# Schaltplan_VoltageLevelShifter_version3_.net
KiCad netlist of a schematic drawn in EAGLE
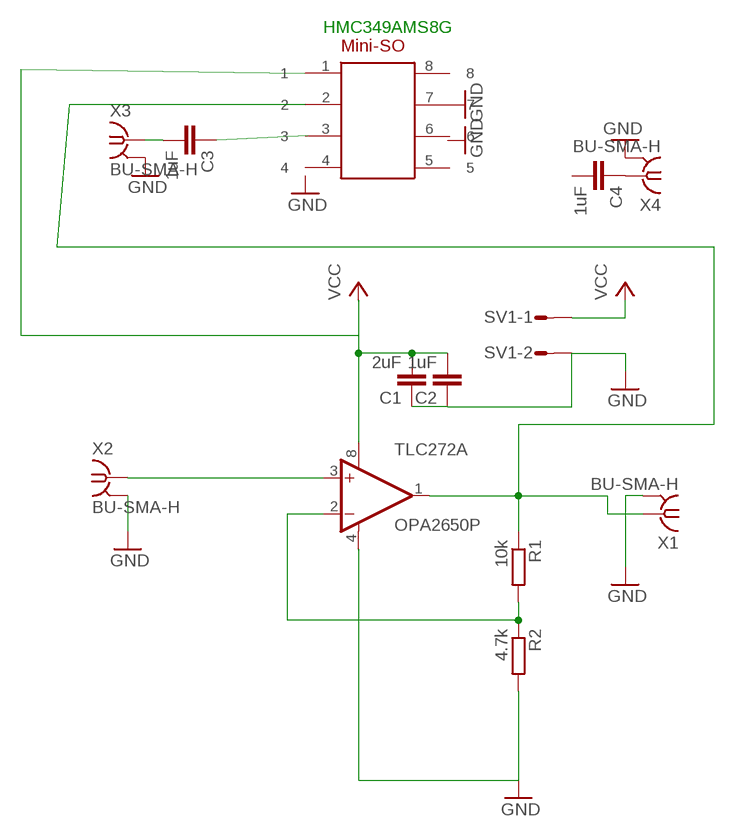
[diagram p0: schematic, sheet 1]

(export (version "E")
  (design (tool "Eeschema 10.0.6"))
  (components
    (comp (ref "C1")
      (value "2uF")
      (footprint "eagle-import:YC7B5")
      (libsource (lib "eagle-import") (part "CYYC7B5"))
    )
    (comp (ref "C2")
      (value "1uF")
      (footprint "eagle-import:YC7B5")
      (libsource (lib "eagle-import") (part "CYYC7B5"))
    )
    (comp (ref "C3")
      (value "1uF")
      (footprint "eagle-import:YC7B5")
      (libsource (lib "eagle-import") (part "CYYC7B5"))
    )
    (comp (ref "C4")
      (value "1uF")
      (footprint "eagle-import:YC7B5")
      (libsource (lib "eagle-import") (part "CYYC7B5"))
    )
    (comp (ref "HMC349AMS8G")
      (value "MINI-SO")
      (footprint "eagle-import:MINI-SO")
      (libsource (lib "eagle-import") (part "MINI-SO"))
    )
    (comp (ref "R1")
      (value "10k")
      (footprint "eagle-import:0207_12")
      (libsource (lib "eagle-import") (part "R-EU_0207/12"))
    )
    (comp (ref "R2")
      (value "4.7k")
      (footprint "eagle-import:0207_12")
      (libsource (lib "eagle-import") (part "R-EU_0207/12"))
    )
    (comp (ref "SV1")
      (value "S02P")
      (footprint "eagle-import:S02P")
      (libsource (lib "eagle-import") (part "S02P"))
    )
    (comp (ref "TLC272")
      (value "OPA2650P")
      (footprint "eagle-import:DIL08")
      (fields (field (name "MPN") "AD8056ANZ"))
      (libsource (lib "eagle-import") (part "OPA2650P"))
    )
    (comp (ref "X1")
      (value "BU-SMA-H")
      (footprint "eagle-import:BU-SMA-H")
      (libsource (lib "eagle-import") (part "BU-SMA-H"))
    )
    (comp (ref "X2")
      (value "BU-SMA-H")
      (footprint "eagle-import:BU-SMA-H")
      (libsource (lib "eagle-import") (part "BU-SMA-H"))
    )
    (comp (ref "X3")
      (value "BU-SMA-H")
      (footprint "eagle-import:BU-SMA-H")
      (libsource (lib "eagle-import") (part "BU-SMA-H"))
    )
    (comp (ref "X4")
      (value "BU-SMA-H")
      (footprint "eagle-import:BU-SMA-H")
      (libsource (lib "eagle-import") (part "BU-SMA-H"))
    )
  )
  (nets
    (net (code "1") (name "GND") (class "Default")
      (node (ref "C1") (pin "1") (pinfunction "1_1") (pintype "passive"))
      (node (ref "C2") (pin "1") (pinfunction "1_1") (pintype "passive"))
      (node (ref "R2") (pin "2") (pinfunction "2_2") (pintype "passive"))
      (node (ref "SV1") (pin "2") (pinfunction "S_2") (pintype "passive"))
      (node (ref "TLC272") (pin "4") (pinfunction "V-_4") (pintype "power_in"))
      (node (ref "X1") (pin "2") (pinfunction "2_2") (pintype "passive"))
      (node (ref "X1") (pin "3") (pinfunction "2_3") (pintype "passive"))
      (node (ref "X1") (pin "4") (pinfunction "2_4") (pintype "passive"))
      (node (ref "X1") (pin "5") (pinfunction "2_5") (pintype "passive"))
      (node (ref "X2") (pin "2") (pinfunction "2_2") (pintype "passive"))
      (node (ref "X2") (pin "3") (pinfunction "2_3") (pintype "passive"))
      (node (ref "X2") (pin "4") (pinfunction "2_4") (pintype "passive"))
      (node (ref "X2") (pin "5") (pinfunction "2_5") (pintype "passive"))
      (node (ref "X3") (pin "2") (pinfunction "2_2") (pintype "passive"))
      (node (ref "X3") (pin "3") (pinfunction "2_3") (pintype "passive"))
      (node (ref "X3") (pin "4") (pinfunction "2_4") (pintype "passive"))
      (node (ref "X3") (pin "5") (pinfunction "2_5") (pintype "passive"))
      (node (ref "X4") (pin "2") (pinfunction "2_2") (pintype "passive"))
      (node (ref "X4") (pin "3") (pinfunction "2_3") (pintype "passive"))
      (node (ref "X4") (pin "4") (pinfunction "2_4") (pintype "passive"))
      (node (ref "X4") (pin "5") (pinfunction "2_5") (pintype "passive"))
    )
    (net (code "2") (name "Net-(C3-Pad2)") (class "Default")
      (node (ref "C3") (pin "2") (pinfunction "2_2") (pintype "passive"))
      (node (ref "X3") (pin "1") (pinfunction "1_1") (pintype "passive"))
    )
    (net (code "3") (name "Net-(C4-Pad1)") (class "Default")
      (node (ref "C4") (pin "1") (pinfunction "1_1") (pintype "passive"))
      (node (ref "X4") (pin "1") (pinfunction "1_1") (pintype "passive"))
    )
    (net (code "4") (name "Net-(TLC272A-+IN)") (class "Default")
      (node (ref "TLC272") (pin "3") (pinfunction "+IN_3") (pintype "input"))
      (node (ref "X2") (pin "1") (pinfunction "1_1") (pintype "passive"))
    )
    (net (code "5") (name "Net-(TLC272A--IN)") (class "Default")
      (node (ref "R1") (pin "2") (pinfunction "2_2") (pintype "passive"))
      (node (ref "R2") (pin "1") (pinfunction "1_1") (pintype "passive"))
      (node (ref "TLC272") (pin "2") (pinfunction "-IN_2") (pintype "input"))
    )
    (net (code "6") (name "Net-(TLC272A-OUT)") (class "Default")
      (node (ref "R1") (pin "1") (pinfunction "1_1") (pintype "passive"))
      (node (ref "TLC272") (pin "1") (pinfunction "OUT_1") (pintype "output"))
      (node (ref "X1") (pin "1") (pinfunction "1_1") (pintype "passive"))
    )
    (net (code "7") (name "VCC") (class "Default")
      (node (ref "C1") (pin "2") (pinfunction "2_2") (pintype "passive"))
      (node (ref "C2") (pin "2") (pinfunction "2_2") (pintype "passive"))
      (node (ref "SV1") (pin "1") (pinfunction "S_1") (pintype "passive"))
      (node (ref "TLC272") (pin "8") (pinfunction "V+_8") (pintype "power_in"))
    )
    (net (code "8") (name "unconnected-(C3-Pad1)") (class "Default")
      (node (ref "C3") (pin "1") (pinfunction "1_1") (pintype "passive"))
    )
    (net (code "9") (name "unconnected-(C4-Pad2)") (class "Default")
      (node (ref "C4") (pin "2") (pinfunction "2_2") (pintype "passive"))
    )
    (net (code "10") (name "unconnected-(HMC349AMS8G-Pad1)") (class "Default")
      (node (ref "HMC349AMS8G") (pin "1") (pinfunction "1_1") (pintype "bidirectional"))
    )
    (net (code "11") (name "unconnected-(HMC349AMS8G-Pad2)") (class "Default")
      (node (ref "HMC349AMS8G") (pin "2") (pinfunction "2_2") (pintype "bidirectional"))
    )
    (net (code "12") (name "unconnected-(HMC349AMS8G-Pad3)") (class "Default")
      (node (ref "HMC349AMS8G") (pin "3") (pinfunction "3_3") (pintype "bidirectional"))
    )
    (net (code "13") (name "unconnected-(HMC349AMS8G-Pad4)") (class "Default")
      (node (ref "HMC349AMS8G") (pin "4") (pinfunction "4_4") (pintype "bidirectional"))
    )
    (net (code "14") (name "unconnected-(HMC349AMS8G-Pad5)") (class "Default")
      (node (ref "HMC349AMS8G") (pin "5") (pinfunction "5_5") (pintype "bidirectional"))
    )
    (net (code "15") (name "unconnected-(HMC349AMS8G-Pad6)") (class "Default")
      (node (ref "HMC349AMS8G") (pin "6") (pinfunction "6_6") (pintype "bidirectional"))
    )
    (net (code "16") (name "unconnected-(HMC349AMS8G-Pad7)") (class "Default")
      (node (ref "HMC349AMS8G") (pin "7") (pinfunction "7_7") (pintype "bidirectional"))
    )
    (net (code "17") (name "unconnected-(HMC349AMS8G-Pad8)") (class "Default")
      (node (ref "HMC349AMS8G") (pin "8") (pinfunction "8_8") (pintype "bidirectional"))
    )
  )
)
